# GNSS_Chip_Antenna_Evaluation_Board.net
KiCad netlist of a schematic drawn in EAGLE
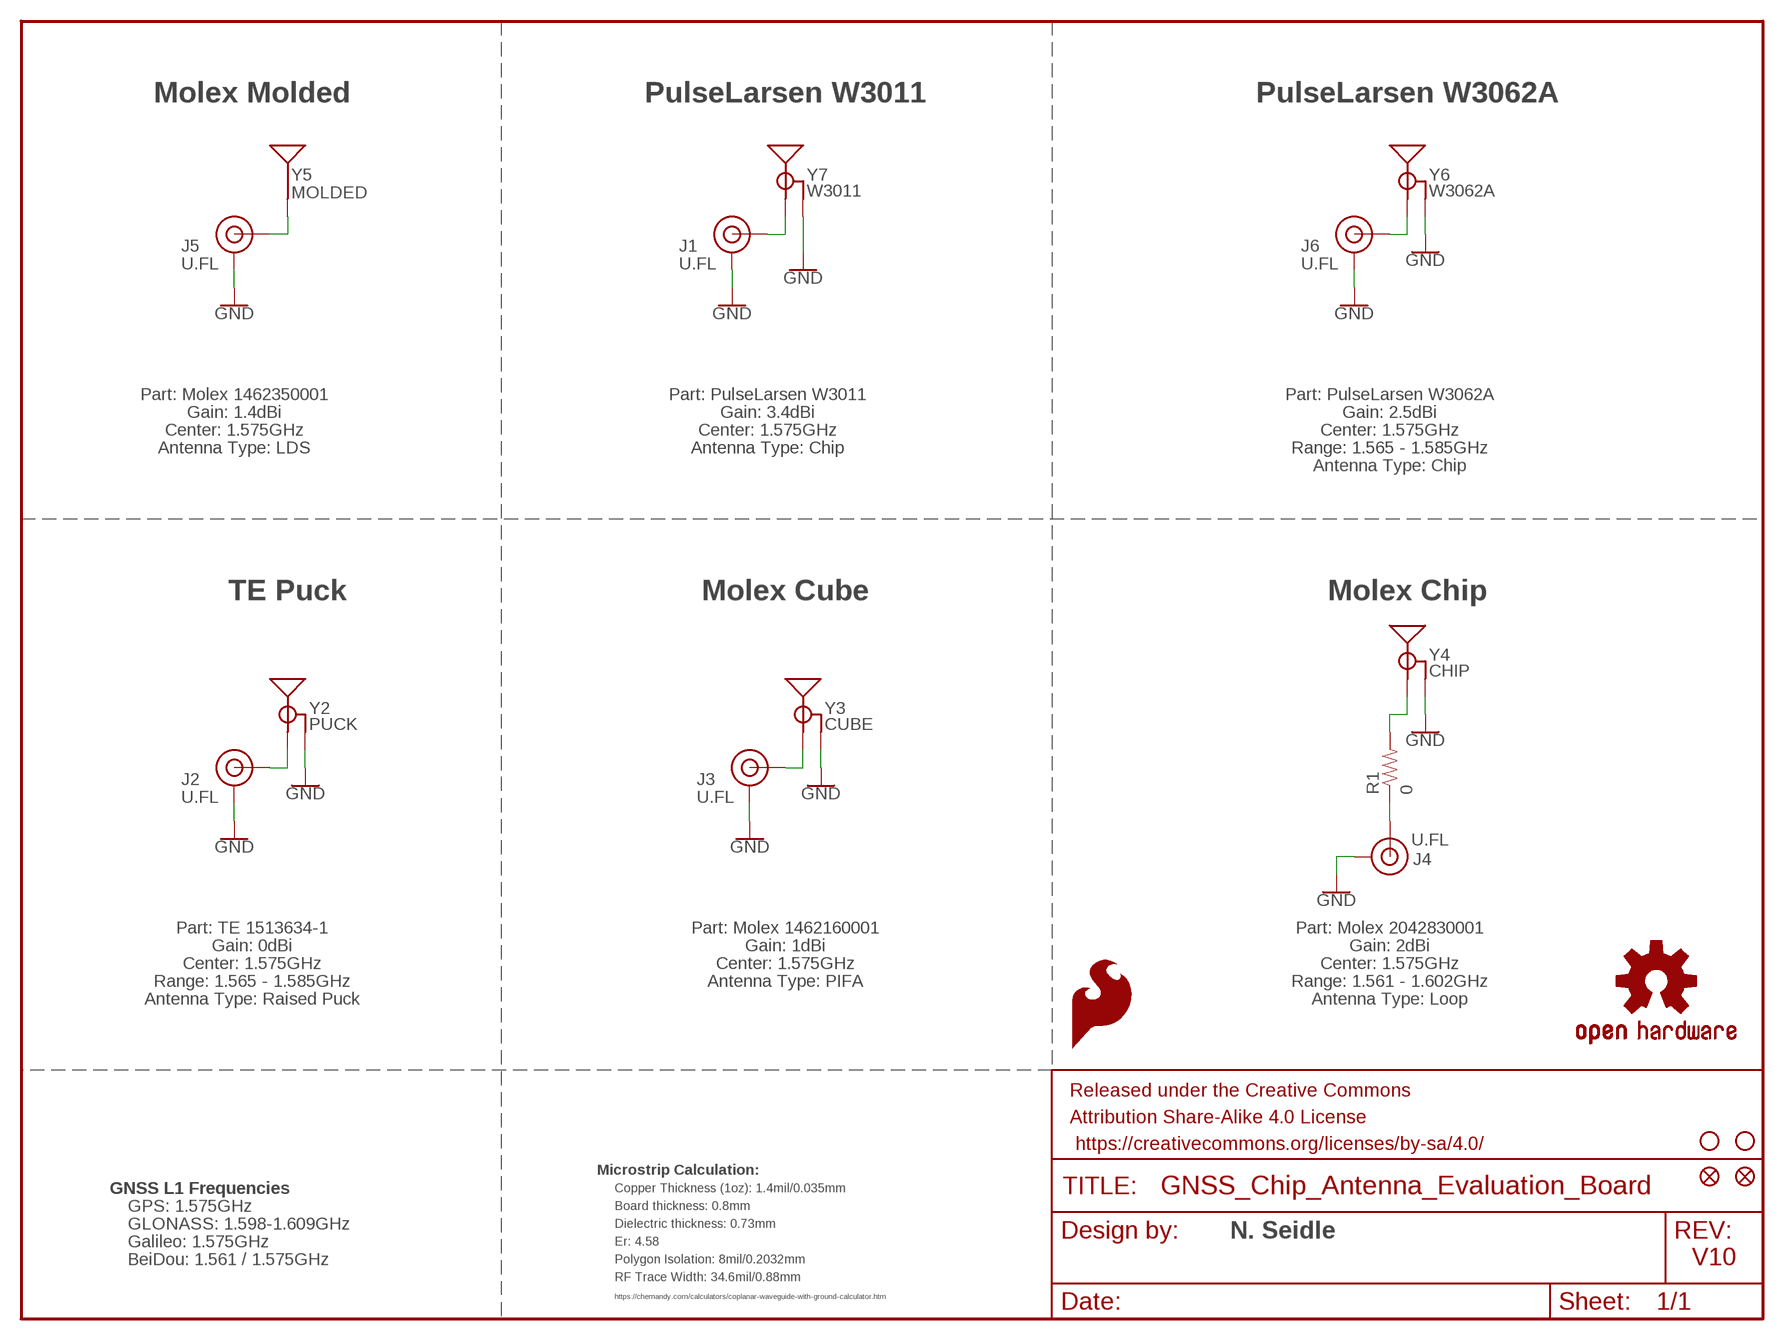
[diagram p0: schematic, sheet 1]

(export (version "E")
  (design (tool "Eeschema 10.0.6"))
  (components
    (comp (ref "FRAME1")
      (value "FRAME-LETTER")
      (footprint "eagle-import:CREATIVE_COMMONS")
      (libsource (lib "eagle-import") (part "FRAME-LETTER"))
    )
    (comp (ref "J1")
      (value "U.FL")
      (footprint "eagle-import:U.FL")
      (libsource (lib "eagle-import") (part "U.FL2PIN"))
    )
    (comp (ref "J2")
      (value "U.FL")
      (footprint "eagle-import:U.FL")
      (libsource (lib "eagle-import") (part "U.FL2PIN"))
    )
    (comp (ref "J3")
      (value "U.FL")
      (footprint "eagle-import:U.FL")
      (libsource (lib "eagle-import") (part "U.FL2PIN"))
    )
    (comp (ref "J4")
      (value "U.FL")
      (footprint "eagle-import:U.FL")
      (libsource (lib "eagle-import") (part "U.FL2PIN"))
    )
    (comp (ref "J5")
      (value "U.FL")
      (footprint "eagle-import:U.FL")
      (libsource (lib "eagle-import") (part "U.FL2PIN"))
    )
    (comp (ref "J6")
      (value "U.FL")
      (footprint "eagle-import:U.FL")
      (libsource (lib "eagle-import") (part "U.FL2PIN"))
    )
    (comp (ref "JP5")
      (value "STAND-OFF")
      (footprint "eagle-import:STAND-OFF")
      (libsource (lib "eagle-import") (part "STAND-OFF"))
    )
    (comp (ref "JP6")
      (value "STAND-OFF")
      (footprint "eagle-import:STAND-OFF")
      (libsource (lib "eagle-import") (part "STAND-OFF"))
    )
    (comp (ref "JP8")
      (value "FIDUCIAL1X2")
      (footprint "eagle-import:FIDUCIAL-1X2")
      (libsource (lib "eagle-import") (part "FIDUCIAL1X2"))
    )
    (comp (ref "JP9")
      (value "FIDUCIAL1X2")
      (footprint "eagle-import:FIDUCIAL-1X2")
      (libsource (lib "eagle-import") (part "FIDUCIAL1X2"))
    )
    (comp (ref "LOGO1")
      (value "SFE_LOGO_FLAME.1EXP")
      (footprint "eagle-import:SFE_LOGO_FLAME_COPPER_EXPOSED_.1")
      (libsource (lib "eagle-import") (part "SFE_LOGO_FLAME.1EXP"))
    )
    (comp (ref "LOGO2")
      (value "SFE_LOGO_FLAME.1EXP")
      (footprint "eagle-import:SFE_LOGO_FLAME_COPPER_EXPOSED_.1")
      (libsource (lib "eagle-import") (part "SFE_LOGO_FLAME.1EXP"))
    )
    (comp (ref "LOGO3")
      (value "SFE_LOGO_FLAME.1EXP")
      (footprint "eagle-import:SFE_LOGO_FLAME_COPPER_EXPOSED_.1")
      (libsource (lib "eagle-import") (part "SFE_LOGO_FLAME.1EXP"))
    )
    (comp (ref "LOGO4")
      (value "SFE_LOGO_FLAME.1EXP")
      (footprint "eagle-import:SFE_LOGO_FLAME_COPPER_EXPOSED_.1")
      (libsource (lib "eagle-import") (part "SFE_LOGO_FLAME.1EXP"))
    )
    (comp (ref "LOGO5")
      (value "SFE_LOGO_FLAME.1EXP")
      (footprint "eagle-import:SFE_LOGO_FLAME_COPPER_EXPOSED_.1")
      (libsource (lib "eagle-import") (part "SFE_LOGO_FLAME.1EXP"))
    )
    (comp (ref "LOGO6")
      (value "SFE_LOGO_FLAME.1EXP")
      (footprint "eagle-import:SFE_LOGO_FLAME_COPPER_EXPOSED_.1")
      (libsource (lib "eagle-import") (part "SFE_LOGO_FLAME.1EXP"))
    )
    (comp (ref "R1")
      (value "0")
      (footprint "eagle-import:0402")
      (libsource (lib "eagle-import") (part "0OHM-0402-1/10W"))
    )
    (comp (ref "U$16")
      (value "OSHW-LOGOS")
      (footprint "eagle-import:OSHW-LOGO-S")
      (libsource (lib "eagle-import") (part "OSHW-LOGOS"))
    )
    (comp (ref "Y2")
      (value "PUCK")
      (footprint "eagle-import:TE_PUCK")
      (libsource (lib "eagle-import") (part "GPS_CHIP_ANTENNAPUCK"))
    )
    (comp (ref "Y3")
      (value "CUBE")
      (footprint "eagle-import:MOLEX_GNSS_CUBE")
      (libsource (lib "eagle-import") (part "GPS_CHIP_ANTENNACUBE"))
    )
    (comp (ref "Y4")
      (value "CHIP")
      (footprint "eagle-import:MOLEX_GNSS_CHIP")
      (libsource (lib "eagle-import") (part "GPS_CHIP_ANTENNA2042830001"))
    )
    (comp (ref "Y5")
      (value "MOLDED")
      (footprint "eagle-import:MLOEX_GNSS_MOLDED")
      (libsource (lib "eagle-import") (part "GPS_CHIP_ANTENNA_NOGNDMOLDED"))
    )
    (comp (ref "Y6")
      (value "W3062A")
      (footprint "eagle-import:W3062A")
      (libsource (lib "eagle-import") (part "GPS_CHIP_ANTENNAW3062A"))
    )
    (comp (ref "Y7")
      (value "W3011")
      (footprint "eagle-import:W3011")
      (libsource (lib "eagle-import") (part "GPS_CHIP_ANTENNAW3011"))
    )
  )
  (nets
    (net (code "1") (name "GND") (class "Default")
      (node (ref "J1") (pin "1") (pinfunction "GND_1") (pintype "bidirectional"))
      (node (ref "J1") (pin "2") (pinfunction "GND_2") (pintype "bidirectional"))
      (node (ref "J2") (pin "1") (pinfunction "GND_1") (pintype "bidirectional"))
      (node (ref "J2") (pin "2") (pinfunction "GND_2") (pintype "bidirectional"))
      (node (ref "J3") (pin "1") (pinfunction "GND_1") (pintype "bidirectional"))
      (node (ref "J3") (pin "2") (pinfunction "GND_2") (pintype "bidirectional"))
      (node (ref "J4") (pin "1") (pinfunction "GND_1") (pintype "bidirectional"))
      (node (ref "J4") (pin "2") (pinfunction "GND_2") (pintype "bidirectional"))
      (node (ref "J5") (pin "1") (pinfunction "GND_1") (pintype "bidirectional"))
      (node (ref "J5") (pin "2") (pinfunction "GND_2") (pintype "bidirectional"))
      (node (ref "J6") (pin "1") (pinfunction "GND_1") (pintype "bidirectional"))
      (node (ref "J6") (pin "2") (pinfunction "GND_2") (pintype "bidirectional"))
      (node (ref "Y2") (pin "1") (pinfunction "GND_1") (pintype "bidirectional"))
      (node (ref "Y2") (pin "2") (pinfunction "GND_2") (pintype "bidirectional"))
      (node (ref "Y2") (pin "3") (pinfunction "GND_3") (pintype "bidirectional"))
      (node (ref "Y3") (pin "GND") (pinfunction "GND_GND") (pintype "bidirectional"))
      (node (ref "Y4") (pin "1") (pinfunction "GND_1") (pintype "bidirectional"))
      (node (ref "Y4") (pin "2") (pinfunction "GND_2") (pintype "bidirectional"))
      (node (ref "Y4") (pin "3") (pinfunction "GND_3") (pintype "bidirectional"))
      (node (ref "Y6") (pin "GND") (pinfunction "GND_GND") (pintype "bidirectional"))
      (node (ref "Y7") (pin "2") (pinfunction "GND_2") (pintype "bidirectional"))
      (node (ref "Y7") (pin "3") (pinfunction "GND_3") (pintype "bidirectional"))
    )
    (net (code "2") (name "Net-(J1-SIGNAL)") (class "Default")
      (node (ref "J1") (pin "FEED") (pinfunction "SIGNAL_FEED") (pintype "bidirectional"))
      (node (ref "Y7") (pin "1") (pinfunction "SIGNAL_1") (pintype "bidirectional"))
    )
    (net (code "3") (name "Net-(J2-SIGNAL)") (class "Default")
      (node (ref "J2") (pin "FEED") (pinfunction "SIGNAL_FEED") (pintype "bidirectional"))
      (node (ref "Y2") (pin "S") (pinfunction "SIGNAL_S") (pintype "bidirectional"))
    )
    (net (code "4") (name "Net-(J3-SIGNAL)") (class "Default")
      (node (ref "J3") (pin "FEED") (pinfunction "SIGNAL_FEED") (pintype "bidirectional"))
      (node (ref "Y3") (pin "FEED") (pinfunction "SIGNAL_FEED") (pintype "bidirectional"))
    )
    (net (code "5") (name "Net-(J4-SIGNAL)") (class "Default")
      (node (ref "J4") (pin "FEED") (pinfunction "SIGNAL_FEED") (pintype "bidirectional"))
      (node (ref "R1") (pin "1") (pinfunction "1_1") (pintype "passive"))
    )
    (net (code "6") (name "Net-(J5-SIGNAL)") (class "Default")
      (node (ref "J5") (pin "FEED") (pinfunction "SIGNAL_FEED") (pintype "bidirectional"))
      (node (ref "Y5") (pin "FEED") (pinfunction "SIGNAL_FEED") (pintype "bidirectional"))
    )
    (net (code "7") (name "Net-(J6-SIGNAL)") (class "Default")
      (node (ref "J6") (pin "FEED") (pinfunction "SIGNAL_FEED") (pintype "bidirectional"))
      (node (ref "Y6") (pin "FEED") (pinfunction "SIGNAL_FEED") (pintype "bidirectional"))
    )
    (net (code "8") (name "Net-(Y4-SIGNAL)") (class "Default")
      (node (ref "R1") (pin "2") (pinfunction "2_2") (pintype "passive"))
      (node (ref "Y4") (pin "FEED") (pinfunction "SIGNAL_FEED") (pintype "bidirectional"))
    )
  )
)
